# C3D_ReMix_Expansion_-_Extruder_Board.net
KiCad netlist of a schematic drawn in EAGLE
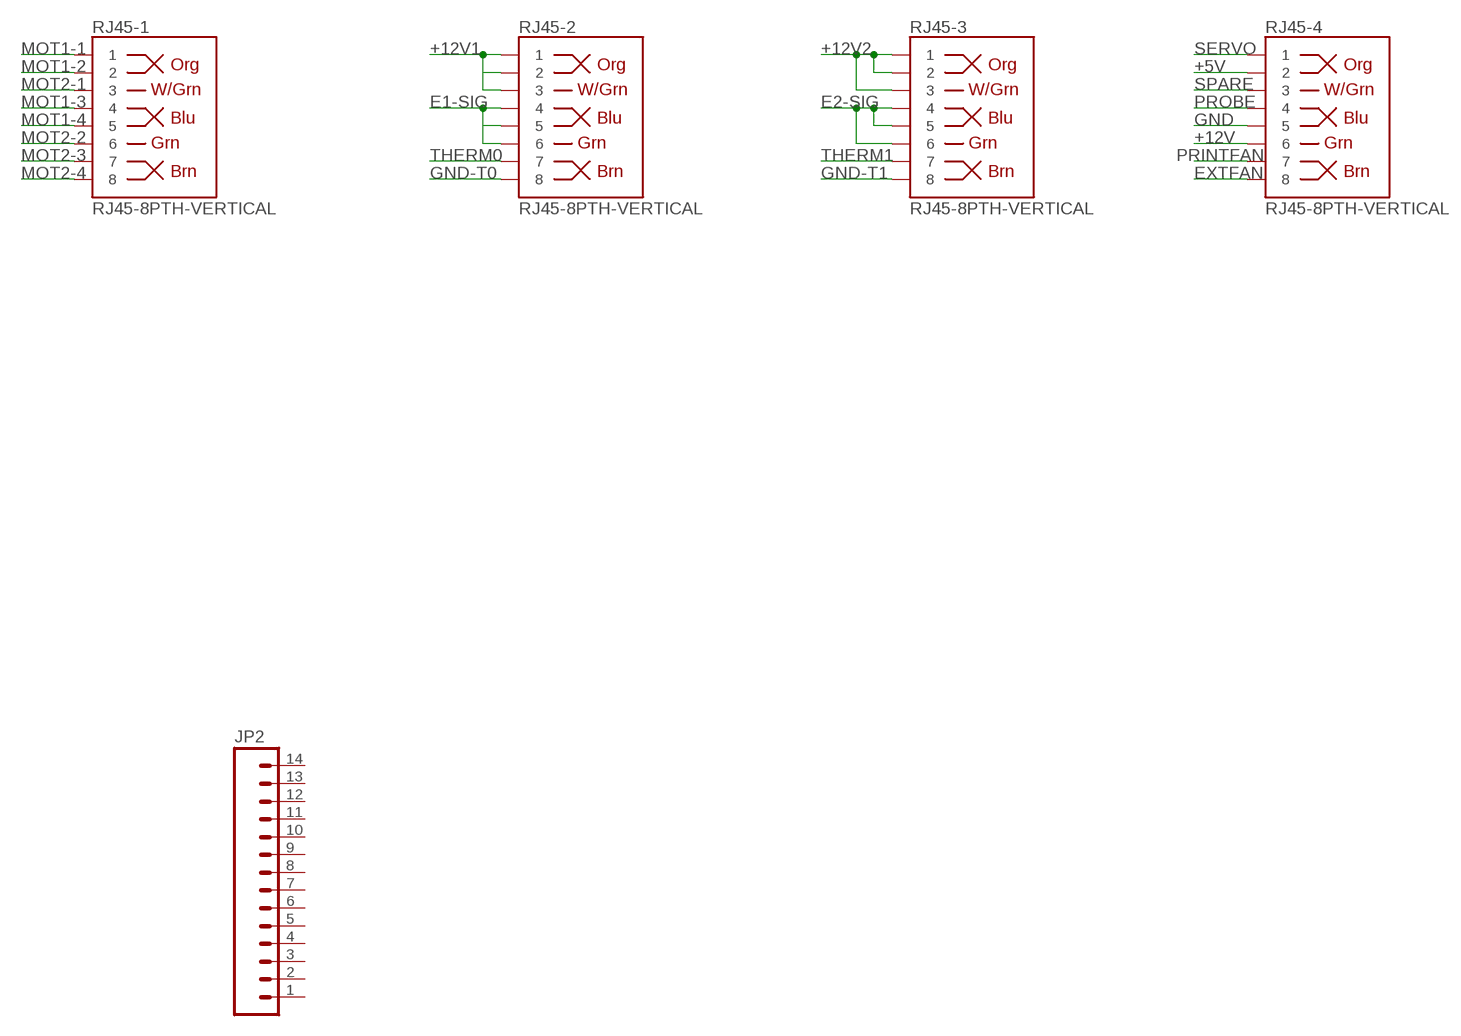
[diagram p0: schematic, sheet 1]

(export (version "E")
  (design (tool "Eeschema 10.0.6"))
  (components
    (comp (ref "JP2")
      (value "M14")
      (footprint "eagle-import:1X14")
      (libsource (lib "eagle-import") (part "M14"))
    )
    (comp (ref "RJ45-1")
      (value "RJ45-8PTH-VERTICAL")
      (footprint "eagle-import:RJ45-8")
      (libsource (lib "eagle-import") (part "RJ45-8PTH-VERTICAL"))
    )
    (comp (ref "RJ45-2")
      (value "RJ45-8PTH-VERTICAL")
      (footprint "eagle-import:RJ45-8")
      (libsource (lib "eagle-import") (part "RJ45-8PTH-VERTICAL"))
    )
    (comp (ref "RJ45-3")
      (value "RJ45-8PTH-VERTICAL")
      (footprint "eagle-import:RJ45-8")
      (libsource (lib "eagle-import") (part "RJ45-8PTH-VERTICAL"))
    )
    (comp (ref "RJ45-4")
      (value "RJ45-8PTH-VERTICAL")
      (footprint "eagle-import:RJ45-8")
      (libsource (lib "eagle-import") (part "RJ45-8PTH-VERTICAL"))
    )
  )
  (nets
    (net (code "1") (name "/+5V") (class "Default")
      (node (ref "RJ45-4") (pin "2") (pinfunction "2_2") (pintype "bidirectional"))
    )
    (net (code "2") (name "/+12V") (class "Default")
      (node (ref "RJ45-4") (pin "6") (pinfunction "6_6") (pintype "bidirectional"))
    )
    (net (code "3") (name "/+12V1") (class "Default")
      (node (ref "RJ45-2") (pin "1") (pinfunction "1_1") (pintype "bidirectional"))
      (node (ref "RJ45-2") (pin "2") (pinfunction "2_2") (pintype "bidirectional"))
      (node (ref "RJ45-2") (pin "3") (pinfunction "3_3") (pintype "bidirectional"))
    )
    (net (code "4") (name "/+12V2") (class "Default")
      (node (ref "RJ45-3") (pin "1") (pinfunction "1_1") (pintype "bidirectional"))
      (node (ref "RJ45-3") (pin "2") (pinfunction "2_2") (pintype "bidirectional"))
      (node (ref "RJ45-3") (pin "3") (pinfunction "3_3") (pintype "bidirectional"))
    )
    (net (code "5") (name "/E1-SIG") (class "Default")
      (node (ref "RJ45-2") (pin "4") (pinfunction "4_4") (pintype "bidirectional"))
      (node (ref "RJ45-2") (pin "5") (pinfunction "5_5") (pintype "bidirectional"))
      (node (ref "RJ45-2") (pin "6") (pinfunction "6_6") (pintype "bidirectional"))
    )
    (net (code "6") (name "/E2-SIG") (class "Default")
      (node (ref "RJ45-3") (pin "4") (pinfunction "4_4") (pintype "bidirectional"))
      (node (ref "RJ45-3") (pin "5") (pinfunction "5_5") (pintype "bidirectional"))
      (node (ref "RJ45-3") (pin "6") (pinfunction "6_6") (pintype "bidirectional"))
    )
    (net (code "7") (name "/EXTFAN") (class "Default")
      (node (ref "RJ45-4") (pin "8") (pinfunction "8_8") (pintype "bidirectional"))
    )
    (net (code "8") (name "/GND") (class "Default")
      (node (ref "RJ45-4") (pin "5") (pinfunction "5_5") (pintype "bidirectional"))
    )
    (net (code "9") (name "/GND-T0") (class "Default")
      (node (ref "RJ45-2") (pin "8") (pinfunction "8_8") (pintype "bidirectional"))
    )
    (net (code "10") (name "/GND-T1") (class "Default")
      (node (ref "RJ45-3") (pin "8") (pinfunction "8_8") (pintype "bidirectional"))
    )
    (net (code "11") (name "/MOT1-1") (class "Default")
      (node (ref "RJ45-1") (pin "1") (pinfunction "1_1") (pintype "bidirectional"))
    )
    (net (code "12") (name "/MOT1-2") (class "Default")
      (node (ref "RJ45-1") (pin "2") (pinfunction "2_2") (pintype "bidirectional"))
    )
    (net (code "13") (name "/MOT1-3") (class "Default")
      (node (ref "RJ45-1") (pin "4") (pinfunction "4_4") (pintype "bidirectional"))
    )
    (net (code "14") (name "/MOT1-4") (class "Default")
      (node (ref "RJ45-1") (pin "5") (pinfunction "5_5") (pintype "bidirectional"))
    )
    (net (code "15") (name "/MOT2-1") (class "Default")
      (node (ref "RJ45-1") (pin "3") (pinfunction "3_3") (pintype "bidirectional"))
    )
    (net (code "16") (name "/MOT2-2") (class "Default")
      (node (ref "RJ45-1") (pin "6") (pinfunction "6_6") (pintype "bidirectional"))
    )
    (net (code "17") (name "/MOT2-3") (class "Default")
      (node (ref "RJ45-1") (pin "7") (pinfunction "7_7") (pintype "bidirectional"))
    )
    (net (code "18") (name "/MOT2-4") (class "Default")
      (node (ref "RJ45-1") (pin "8") (pinfunction "8_8") (pintype "bidirectional"))
    )
    (net (code "19") (name "/PRINTFAN") (class "Default")
      (node (ref "RJ45-4") (pin "7") (pinfunction "7_7") (pintype "bidirectional"))
    )
    (net (code "20") (name "/PROBE") (class "Default")
      (node (ref "RJ45-4") (pin "4") (pinfunction "4_4") (pintype "bidirectional"))
    )
    (net (code "21") (name "/SERVO") (class "Default")
      (node (ref "RJ45-4") (pin "1") (pinfunction "1_1") (pintype "bidirectional"))
    )
    (net (code "22") (name "/SPARE") (class "Default")
      (node (ref "RJ45-4") (pin "3") (pinfunction "3_3") (pintype "bidirectional"))
    )
    (net (code "23") (name "/THERM0") (class "Default")
      (node (ref "RJ45-2") (pin "7") (pinfunction "7_7") (pintype "bidirectional"))
    )
    (net (code "24") (name "/THERM1") (class "Default")
      (node (ref "RJ45-3") (pin "7") (pinfunction "7_7") (pintype "bidirectional"))
    )
    (net (code "25") (name "unconnected-(JP2-Pad1)") (class "Default")
      (node (ref "JP2") (pin "1") (pinfunction "1_1") (pintype "passive"))
    )
    (net (code "26") (name "unconnected-(JP2-Pad2)") (class "Default")
      (node (ref "JP2") (pin "2") (pinfunction "2_2") (pintype "passive"))
    )
    (net (code "27") (name "unconnected-(JP2-Pad3)") (class "Default")
      (node (ref "JP2") (pin "3") (pinfunction "3_3") (pintype "passive"))
    )
    (net (code "28") (name "unconnected-(JP2-Pad4)") (class "Default")
      (node (ref "JP2") (pin "4") (pinfunction "4_4") (pintype "passive"))
    )
    (net (code "29") (name "unconnected-(JP2-Pad5)") (class "Default")
      (node (ref "JP2") (pin "5") (pinfunction "5_5") (pintype "passive"))
    )
    (net (code "30") (name "unconnected-(JP2-Pad6)") (class "Default")
      (node (ref "JP2") (pin "6") (pinfunction "6_6") (pintype "passive"))
    )
    (net (code "31") (name "unconnected-(JP2-Pad7)") (class "Default")
      (node (ref "JP2") (pin "7") (pinfunction "7_7") (pintype "passive"))
    )
    (net (code "32") (name "unconnected-(JP2-Pad8)") (class "Default")
      (node (ref "JP2") (pin "8") (pinfunction "8_8") (pintype "passive"))
    )
    (net (code "33") (name "unconnected-(JP2-Pad9)") (class "Default")
      (node (ref "JP2") (pin "9") (pinfunction "9_9") (pintype "passive"))
    )
    (net (code "34") (name "unconnected-(JP2-Pad10)") (class "Default")
      (node (ref "JP2") (pin "10") (pinfunction "10_10") (pintype "passive"))
    )
    (net (code "35") (name "unconnected-(JP2-Pad11)") (class "Default")
      (node (ref "JP2") (pin "11") (pinfunction "11_11") (pintype "passive"))
    )
    (net (code "36") (name "unconnected-(JP2-Pad12)") (class "Default")
      (node (ref "JP2") (pin "12") (pinfunction "12_12") (pintype "passive"))
    )
    (net (code "37") (name "unconnected-(JP2-Pad13)") (class "Default")
      (node (ref "JP2") (pin "13") (pinfunction "13_13") (pintype "passive"))
    )
    (net (code "38") (name "unconnected-(JP2-Pad14)") (class "Default")
      (node (ref "JP2") (pin "14") (pinfunction "14_14") (pintype "passive"))
    )
  )
)
